# MosfetBoard.net
KiCad netlist of a schematic drawn in EAGLE
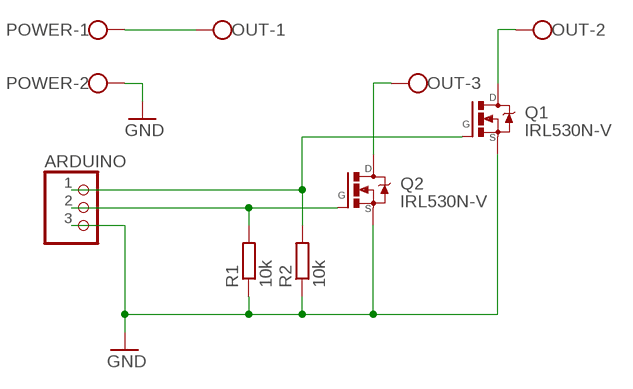
[diagram p0: schematic, sheet 1]

(export (version "E")
  (design (tool "Eeschema 10.0.6"))
  (components
    (comp (ref "ARDUINO")
      (value "PINHD-1X3")
      (footprint "eagle-import:1X03")
      (libsource (lib "eagle-import") (part "PINHD-1X3"))
    )
    (comp (ref "OUT")
      (value "W237-103")
      (footprint "eagle-import:W237-103")
      (fields (field (name "MPN") "237-103"))
      (libsource (lib "eagle-import") (part "W237-103"))
    )
    (comp (ref "POWER")
      (value "W237-102")
      (footprint "eagle-import:W237-102")
      (fields (field (name "MPN") "237-102"))
      (libsource (lib "eagle-import") (part "W237-102"))
    )
    (comp (ref "Q1")
      (value "IRL530N-V")
      (footprint "eagle-import:TO220V")
      (libsource (lib "eagle-import") (part "IRL530N-V"))
    )
    (comp (ref "Q2")
      (value "IRL530N-V")
      (footprint "eagle-import:TO220V")
      (libsource (lib "eagle-import") (part "IRL530N-V"))
    )
    (comp (ref "R1")
      (value "10k")
      (footprint "eagle-import:0207_10")
      (libsource (lib "eagle-import") (part "R-EU_0207/10"))
    )
    (comp (ref "R2")
      (value "10k")
      (footprint "eagle-import:0207_10")
      (libsource (lib "eagle-import") (part "R-EU_0207/10"))
    )
  )
  (nets
    (net (code "1") (name "GND") (class "Default")
      (node (ref "ARDUINO") (pin "3") (pinfunction "3_3") (pintype "passive"))
      (node (ref "POWER") (pin "2") (pinfunction "KL_2") (pintype "passive"))
      (node (ref "Q1") (pin "3") (pinfunction "S_3") (pintype "passive"))
      (node (ref "Q2") (pin "3") (pinfunction "S_3") (pintype "passive"))
      (node (ref "R1") (pin "1") (pinfunction "1_1") (pintype "passive"))
      (node (ref "R2") (pin "1") (pinfunction "1_1") (pintype "passive"))
    )
    (net (code "2") (name "Net-(OUTA-KL)") (class "Default")
      (node (ref "OUT") (pin "1") (pinfunction "KL_1") (pintype "passive"))
      (node (ref "POWER") (pin "1") (pinfunction "KL_1") (pintype "passive"))
    )
    (net (code "3") (name "Net-(OUTB-KL)") (class "Default")
      (node (ref "OUT") (pin "2") (pinfunction "KL_2") (pintype "passive"))
      (node (ref "Q1") (pin "2") (pinfunction "D_2") (pintype "passive"))
    )
    (net (code "4") (name "Net-(OUTC-KL)") (class "Default")
      (node (ref "OUT") (pin "3") (pinfunction "KL_3") (pintype "passive"))
      (node (ref "Q2") (pin "2") (pinfunction "D_2") (pintype "passive"))
    )
    (net (code "5") (name "Net-(Q1-G)") (class "Default")
      (node (ref "ARDUINO") (pin "1") (pinfunction "1_1") (pintype "passive"))
      (node (ref "Q1") (pin "1") (pinfunction "G_1") (pintype "passive"))
      (node (ref "R2") (pin "2") (pinfunction "2_2") (pintype "passive"))
    )
    (net (code "6") (name "Net-(Q2-G)") (class "Default")
      (node (ref "ARDUINO") (pin "2") (pinfunction "2_2") (pintype "passive"))
      (node (ref "Q2") (pin "1") (pinfunction "G_1") (pintype "passive"))
      (node (ref "R1") (pin "2") (pinfunction "2_2") (pintype "passive"))
    )
  )
)
